# T06_preliminarySchematic_v1.net
KiCad netlist of a schematic drawn in EAGLE
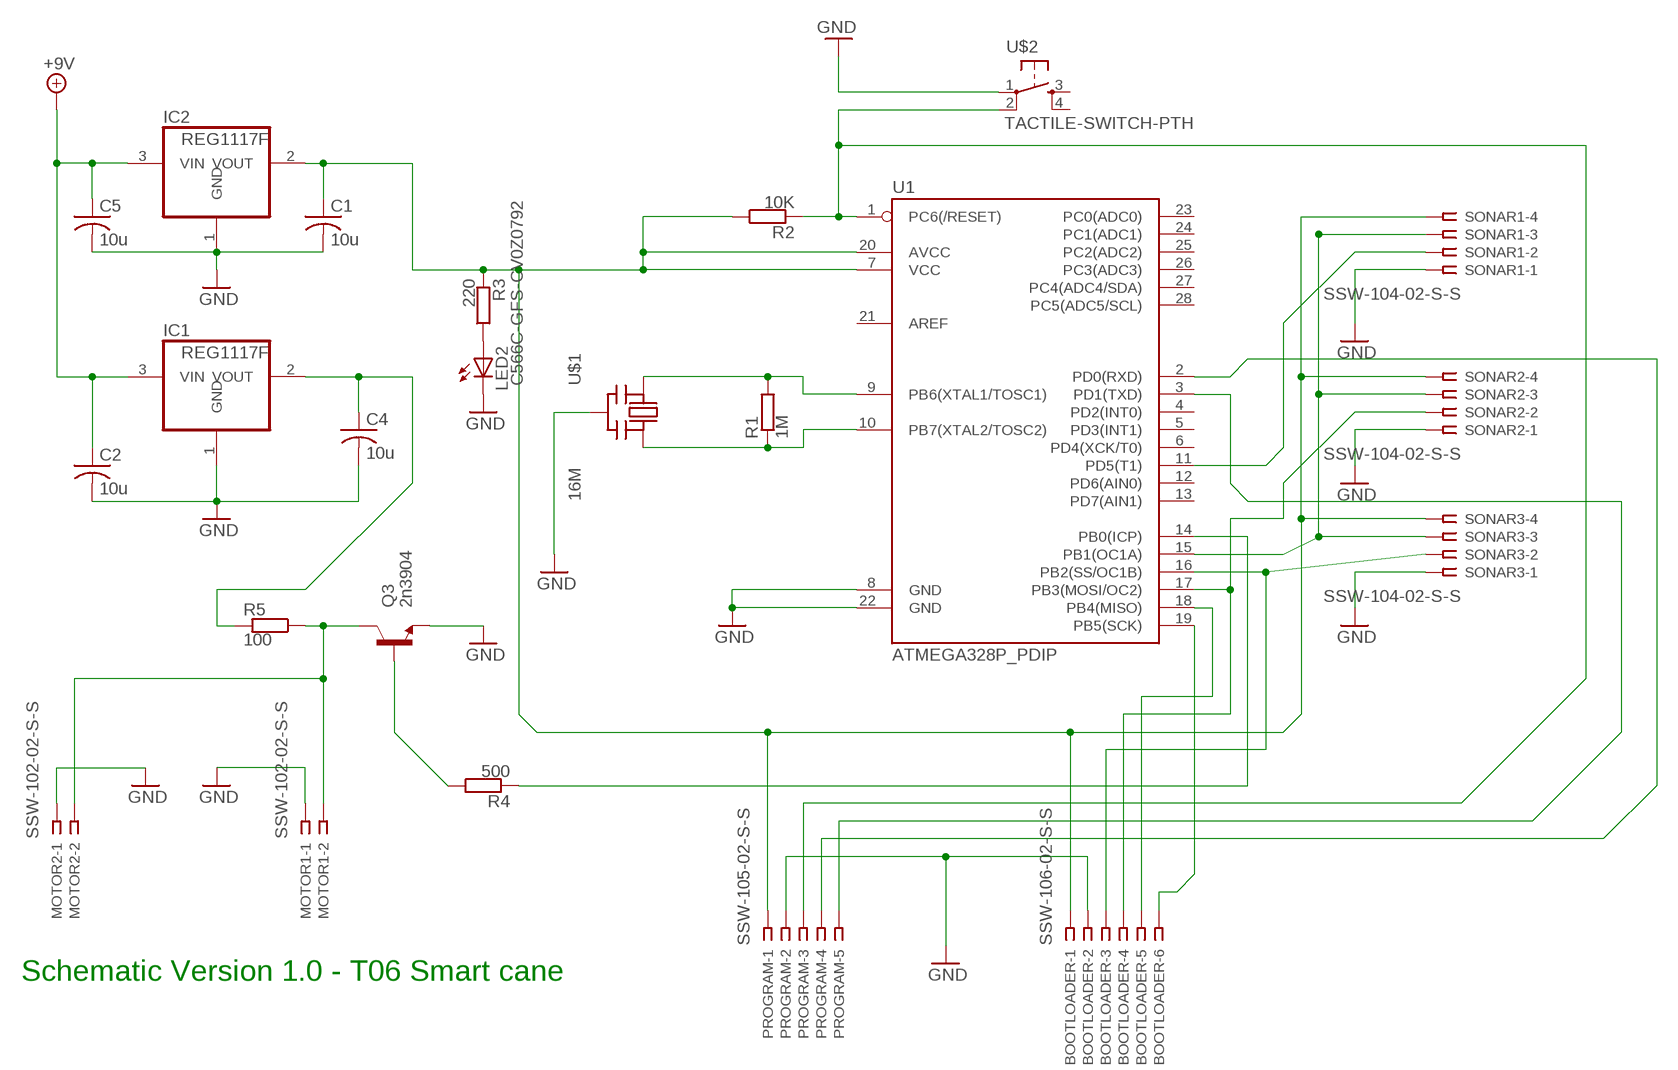
[diagram p0: schematic, sheet 1]

(export (version "E")
  (design (tool "Eeschema 10.0.6"))
  (components
    (comp (ref "BOOTLOADER")
      (value "SSW-106-02-S-S")
      (footprint "eagle-import:SSW-106-02-S-S")
      (libsource (lib "eagle-import") (part "SSW-106-02-S-S"))
    )
    (comp (ref "C1")
      (value "10u")
      (footprint "eagle-import:C0805K")
      (libsource (lib "eagle-import") (part "C-USC0805K"))
    )
    (comp (ref "C2")
      (value "10u")
      (footprint "eagle-import:C0805K")
      (libsource (lib "eagle-import") (part "C-USC0805K"))
    )
    (comp (ref "C4")
      (value "10u")
      (footprint "eagle-import:C0805K")
      (libsource (lib "eagle-import") (part "C-USC0805K"))
    )
    (comp (ref "C5")
      (value "10u")
      (footprint "eagle-import:C0805K")
      (libsource (lib "eagle-import") (part "C-USC0805K"))
    )
    (comp (ref "IC1")
      (value "REG1117F")
      (footprint "eagle-import:DD-3")
      (fields (field (name "MF") "TEXAS INSTRUMENTS") (field (name "MPN") "REG1117FAKTTT"))
      (libsource (lib "eagle-import") (part "REG1117F"))
    )
    (comp (ref "IC2")
      (value "REG1117F")
      (footprint "eagle-import:DD-3")
      (fields (field (name "MF") "TEXAS INSTRUMENTS") (field (name "MPN") "REG1117FAKTTT"))
      (libsource (lib "eagle-import") (part "REG1117F"))
    )
    (comp (ref "LED2")
      (value "C566C-GFS-CV0Z0792")
      (footprint "eagle-import:CHIPLED_1206")
      (libsource (lib "eagle-import") (part "LEDCHIPLED_1206"))
    )
    (comp (ref "MOTOR1")
      (value "SSW-102-02-S-S")
      (footprint "eagle-import:SSW-102-02-S-S")
      (libsource (lib "eagle-import") (part "SSW-102-02-S-S"))
    )
    (comp (ref "MOTOR2")
      (value "SSW-102-02-S-S")
      (footprint "eagle-import:SSW-102-02-S-S")
      (libsource (lib "eagle-import") (part "SSW-102-02-S-S"))
    )
    (comp (ref "PROGRAM")
      (value "SSW-105-02-S-S")
      (footprint "eagle-import:SSW-105-02-S-S")
      (libsource (lib "eagle-import") (part "SSW-105-02-S-S"))
    )
    (comp (ref "Q3")
      (value "2n3904")
      (footprint "eagle-import:TO-92-AMMO")
      (libsource (lib "eagle-import") (part "TRANSISTOR_NPNTO-92-AMMO"))
    )
    (comp (ref "R1")
      (value "1M")
      (footprint "eagle-import:SMR-0")
      (libsource (lib "eagle-import") (part "SMR-0"))
    )
    (comp (ref "R2")
      (value "10K")
      (footprint "eagle-import:SMR-0")
      (libsource (lib "eagle-import") (part "SMR-0"))
    )
    (comp (ref "R3")
      (value "220")
      (footprint "eagle-import:SMR-0")
      (libsource (lib "eagle-import") (part "SMR-0"))
    )
    (comp (ref "R4")
      (value "500")
      (footprint "eagle-import:SMR-0")
      (libsource (lib "eagle-import") (part "SMR-0"))
    )
    (comp (ref "R5")
      (value "100")
      (footprint "eagle-import:SMR-0")
      (libsource (lib "eagle-import") (part "SMR-0"))
    )
    (comp (ref "SONAR1")
      (value "SSW-104-02-S-S")
      (footprint "eagle-import:SSW-104-02-S-S")
      (libsource (lib "eagle-import") (part "SSW-104-02-S-S"))
    )
    (comp (ref "SONAR2")
      (value "SSW-104-02-S-S")
      (footprint "eagle-import:SSW-104-02-S-S")
      (libsource (lib "eagle-import") (part "SSW-104-02-S-S"))
    )
    (comp (ref "SONAR3")
      (value "SSW-104-02-S-S")
      (footprint "eagle-import:SSW-104-02-S-S")
      (libsource (lib "eagle-import") (part "SSW-104-02-S-S"))
    )
    (comp (ref "U$1")
      (value "16M")
      (footprint "eagle-import:CERM_OSC")
      (libsource (lib "eagle-import") (part "CERMOSCILL-THM"))
    )
    (comp (ref "U$2")
      (value "TACTILE-SWITCH-PTH")
      (footprint "eagle-import:TAC-SWITCH-PTH")
      (libsource (lib "eagle-import") (part "TACTILE-SWITCH-PTH"))
    )
    (comp (ref "U1")
      (value "ATMEGA328P_PDIP")
      (footprint "eagle-import:DIL28-3")
      (libsource (lib "eagle-import") (part "ATMEGA328P_PDIP"))
    )
  )
  (nets
    (net (code "1") (name "+9V") (class "Default")
      (node (ref "C2") (pin "1") (pinfunction "1_1") (pintype "passive"))
      (node (ref "C5") (pin "1") (pinfunction "1_1") (pintype "passive"))
      (node (ref "IC1") (pin "3") (pinfunction "VIN_3") (pintype "input"))
      (node (ref "IC2") (pin "3") (pinfunction "VIN_3") (pintype "input"))
    )
    (net (code "2") (name "GND") (class "Default")
      (node (ref "BOOTLOADER") (pin "2") (pinfunction "1_2") (pintype "passive"))
      (node (ref "C1") (pin "2") (pinfunction "2_2") (pintype "passive"))
      (node (ref "C2") (pin "2") (pinfunction "2_2") (pintype "passive"))
      (node (ref "C4") (pin "2") (pinfunction "2_2") (pintype "passive"))
      (node (ref "C5") (pin "2") (pinfunction "2_2") (pintype "passive"))
      (node (ref "IC1") (pin "1") (pinfunction "GND_1") (pintype "power_in"))
      (node (ref "IC2") (pin "1") (pinfunction "GND_1") (pintype "power_in"))
      (node (ref "LED2") (pin "C") (pinfunction "C_C") (pintype "passive"))
      (node (ref "MOTOR1") (pin "1") (pinfunction "1_1") (pintype "passive"))
      (node (ref "MOTOR2") (pin "1") (pinfunction "1_1") (pintype "passive"))
      (node (ref "PROGRAM") (pin "2") (pinfunction "1_2") (pintype "passive"))
      (node (ref "Q3") (pin "1") (pinfunction "E_1") (pintype "passive"))
      (node (ref "SONAR1") (pin "1") (pinfunction "1_1") (pintype "passive"))
      (node (ref "SONAR2") (pin "1") (pinfunction "1_1") (pintype "passive"))
      (node (ref "SONAR3") (pin "1") (pinfunction "1_1") (pintype "passive"))
      (node (ref "U$1") (pin "P$2") (pinfunction "GND_P$2") (pintype "bidirectional"))
      (node (ref "U$2") (pin "1") (pinfunction "1_1") (pintype "passive"))
      (node (ref "U1") (pin "22") (pinfunction "GND_22") (pintype "bidirectional"))
      (node (ref "U1") (pin "8") (pinfunction "GND_8") (pintype "bidirectional"))
    )
    (net (code "3") (name "Net-(BOOTLOADERC-1)") (class "Default")
      (node (ref "BOOTLOADER") (pin "3") (pinfunction "1_3") (pintype "passive"))
      (node (ref "SONAR3") (pin "2") (pinfunction "1_2") (pintype "passive"))
      (node (ref "U1") (pin "16") (pinfunction "PB2(SS/OC1B)_16") (pintype "bidirectional"))
    )
    (net (code "4") (name "Net-(BOOTLOADERD-1)") (class "Default")
      (node (ref "BOOTLOADER") (pin "4") (pinfunction "1_4") (pintype "passive"))
      (node (ref "SONAR2") (pin "2") (pinfunction "1_2") (pintype "passive"))
      (node (ref "U1") (pin "17") (pinfunction "PB3(MOSI/OC2)_17") (pintype "bidirectional"))
    )
    (net (code "5") (name "Net-(BOOTLOADERE-1)") (class "Default")
      (node (ref "BOOTLOADER") (pin "5") (pinfunction "1_5") (pintype "passive"))
      (node (ref "U1") (pin "18") (pinfunction "PB4(MISO)_18") (pintype "bidirectional"))
    )
    (net (code "6") (name "Net-(BOOTLOADERF-1)") (class "Default")
      (node (ref "BOOTLOADER") (pin "6") (pinfunction "1_6") (pintype "passive"))
      (node (ref "U1") (pin "19") (pinfunction "PB5(SCK)_19") (pintype "bidirectional"))
    )
    (net (code "7") (name "Net-(IC1-VOUT)") (class "Default")
      (node (ref "C4") (pin "1") (pinfunction "1_1") (pintype "passive"))
      (node (ref "IC1") (pin "2") (pinfunction "VOUT_2") (pintype "output"))
      (node (ref "R5") (pin "2") (pinfunction "2_2") (pintype "passive"))
    )
    (net (code "8") (name "Net-(IC2-VOUT)") (class "Default")
      (node (ref "BOOTLOADER") (pin "1") (pinfunction "1_1") (pintype "passive"))
      (node (ref "C1") (pin "1") (pinfunction "1_1") (pintype "passive"))
      (node (ref "IC2") (pin "2") (pinfunction "VOUT_2") (pintype "output"))
      (node (ref "PROGRAM") (pin "1") (pinfunction "1_1") (pintype "passive"))
      (node (ref "R2") (pin "1") (pinfunction "1_1") (pintype "passive"))
      (node (ref "R3") (pin "2") (pinfunction "2_2") (pintype "passive"))
      (node (ref "SONAR1") (pin "4") (pinfunction "1_4") (pintype "passive"))
      (node (ref "SONAR2") (pin "4") (pinfunction "1_4") (pintype "passive"))
      (node (ref "SONAR3") (pin "4") (pinfunction "1_4") (pintype "passive"))
      (node (ref "U1") (pin "20") (pinfunction "AVCC_20") (pintype "bidirectional"))
      (node (ref "U1") (pin "7") (pinfunction "VCC_7") (pintype "bidirectional"))
    )
    (net (code "9") (name "Net-(LED2-PadA)") (class "Default")
      (node (ref "LED2") (pin "A") (pinfunction "A_A") (pintype "passive"))
      (node (ref "R3") (pin "1") (pinfunction "1_1") (pintype "passive"))
    )
    (net (code "10") (name "Net-(MOTOR1B-1)") (class "Default")
      (node (ref "MOTOR1") (pin "2") (pinfunction "1_2") (pintype "passive"))
      (node (ref "MOTOR2") (pin "2") (pinfunction "1_2") (pintype "passive"))
      (node (ref "Q3") (pin "3") (pinfunction "C_3") (pintype "passive"))
      (node (ref "R5") (pin "1") (pinfunction "1_1") (pintype "passive"))
    )
    (net (code "11") (name "Net-(PROGRAMC-1)") (class "Default")
      (node (ref "PROGRAM") (pin "3") (pinfunction "1_3") (pintype "passive"))
      (node (ref "R2") (pin "2") (pinfunction "2_2") (pintype "passive"))
      (node (ref "U$2") (pin "2") (pinfunction "2_2") (pintype "passive"))
      (node (ref "U1") (pin "1") (pinfunction "PC6(/RESET)_1") (pintype "bidirectional"))
    )
    (net (code "12") (name "Net-(PROGRAMD-1)") (class "Default")
      (node (ref "PROGRAM") (pin "4") (pinfunction "1_4") (pintype "passive"))
      (node (ref "U1") (pin "2") (pinfunction "PD0(RXD)_2") (pintype "bidirectional"))
    )
    (net (code "13") (name "Net-(PROGRAME-1)") (class "Default")
      (node (ref "PROGRAM") (pin "5") (pinfunction "1_5") (pintype "passive"))
      (node (ref "U1") (pin "3") (pinfunction "PD1(TXD)_3") (pintype "bidirectional"))
    )
    (net (code "14") (name "Net-(Q3-B)") (class "Default")
      (node (ref "Q3") (pin "2") (pinfunction "B_2") (pintype "passive"))
      (node (ref "R4") (pin "1") (pinfunction "1_1") (pintype "passive"))
    )
    (net (code "15") (name "Net-(SONAR1B-1)") (class "Default")
      (node (ref "SONAR1") (pin "2") (pinfunction "1_2") (pintype "passive"))
      (node (ref "U1") (pin "11") (pinfunction "PD5(T1)_11") (pintype "bidirectional"))
    )
    (net (code "16") (name "Net-(SONAR1C-1)") (class "Default")
      (node (ref "SONAR1") (pin "3") (pinfunction "1_3") (pintype "passive"))
      (node (ref "SONAR2") (pin "3") (pinfunction "1_3") (pintype "passive"))
      (node (ref "SONAR3") (pin "3") (pinfunction "1_3") (pintype "passive"))
      (node (ref "U1") (pin "15") (pinfunction "PB1(OC1A)_15") (pintype "bidirectional"))
    )
    (net (code "17") (name "Net-(U$1-IN)") (class "Default")
      (node (ref "R1") (pin "1") (pinfunction "1_1") (pintype "passive"))
      (node (ref "U$1") (pin "P$1") (pinfunction "IN_P$1") (pintype "bidirectional"))
      (node (ref "U1") (pin "9") (pinfunction "PB6(XTAL1/TOSC1)_9") (pintype "bidirectional"))
    )
    (net (code "18") (name "Net-(U$1-OUT)") (class "Default")
      (node (ref "R1") (pin "2") (pinfunction "2_2") (pintype "passive"))
      (node (ref "U$1") (pin "P$3") (pinfunction "OUT_P$3") (pintype "bidirectional"))
      (node (ref "U1") (pin "10") (pinfunction "PB7(XTAL2/TOSC2)_10") (pintype "bidirectional"))
    )
    (net (code "19") (name "Net-(U1-PB0(ICP))") (class "Default")
      (node (ref "R4") (pin "2") (pinfunction "2_2") (pintype "passive"))
      (node (ref "U1") (pin "14") (pinfunction "PB0(ICP)_14") (pintype "bidirectional"))
    )
    (net (code "20") (name "unconnected-(U$2-Pad3)") (class "Default")
      (node (ref "U$2") (pin "3") (pinfunction "3_3") (pintype "passive"))
    )
    (net (code "21") (name "unconnected-(U$2-Pad4)") (class "Default")
      (node (ref "U$2") (pin "4") (pinfunction "4_4") (pintype "passive"))
    )
    (net (code "22") (name "unconnected-(U1-AREF-Pad21)") (class "Default")
      (node (ref "U1") (pin "21") (pinfunction "AREF_21") (pintype "bidirectional"))
    )
    (net (code "23") (name "unconnected-(U1-PC0(ADC0)-Pad23)") (class "Default")
      (node (ref "U1") (pin "23") (pinfunction "PC0(ADC0)_23") (pintype "bidirectional"))
    )
    (net (code "24") (name "unconnected-(U1-PC1(ADC1)-Pad24)") (class "Default")
      (node (ref "U1") (pin "24") (pinfunction "PC1(ADC1)_24") (pintype "bidirectional"))
    )
    (net (code "25") (name "unconnected-(U1-PC2(ADC2)-Pad25)") (class "Default")
      (node (ref "U1") (pin "25") (pinfunction "PC2(ADC2)_25") (pintype "bidirectional"))
    )
    (net (code "26") (name "unconnected-(U1-PC3(ADC3)-Pad26)") (class "Default")
      (node (ref "U1") (pin "26") (pinfunction "PC3(ADC3)_26") (pintype "bidirectional"))
    )
    (net (code "27") (name "unconnected-(U1-PC4(ADC4{slash}SDA)-Pad27)") (class "Default")
      (node (ref "U1") (pin "27") (pinfunction "PC4(ADC4/SDA)_27") (pintype "bidirectional"))
    )
    (net (code "28") (name "unconnected-(U1-PC5(ADC5{slash}SCL)-Pad28)") (class "Default")
      (node (ref "U1") (pin "28") (pinfunction "PC5(ADC5/SCL)_28") (pintype "bidirectional"))
    )
    (net (code "29") (name "unconnected-(U1-PD2(INT0)-Pad4)") (class "Default")
      (node (ref "U1") (pin "4") (pinfunction "PD2(INT0)_4") (pintype "bidirectional"))
    )
    (net (code "30") (name "unconnected-(U1-PD3(INT1)-Pad5)") (class "Default")
      (node (ref "U1") (pin "5") (pinfunction "PD3(INT1)_5") (pintype "bidirectional"))
    )
    (net (code "31") (name "unconnected-(U1-PD4(XCK{slash}T0)-Pad6)") (class "Default")
      (node (ref "U1") (pin "6") (pinfunction "PD4(XCK/T0)_6") (pintype "bidirectional"))
    )
    (net (code "32") (name "unconnected-(U1-PD6(AIN0)-Pad12)") (class "Default")
      (node (ref "U1") (pin "12") (pinfunction "PD6(AIN0)_12") (pintype "bidirectional"))
    )
    (net (code "33") (name "unconnected-(U1-PD7(AIN1)-Pad13)") (class "Default")
      (node (ref "U1") (pin "13") (pinfunction "PD7(AIN1)_13") (pintype "bidirectional"))
    )
  )
)
